# PCB_Project_Board_4.net
KiCad netlist of a schematic drawn in Altium Designer
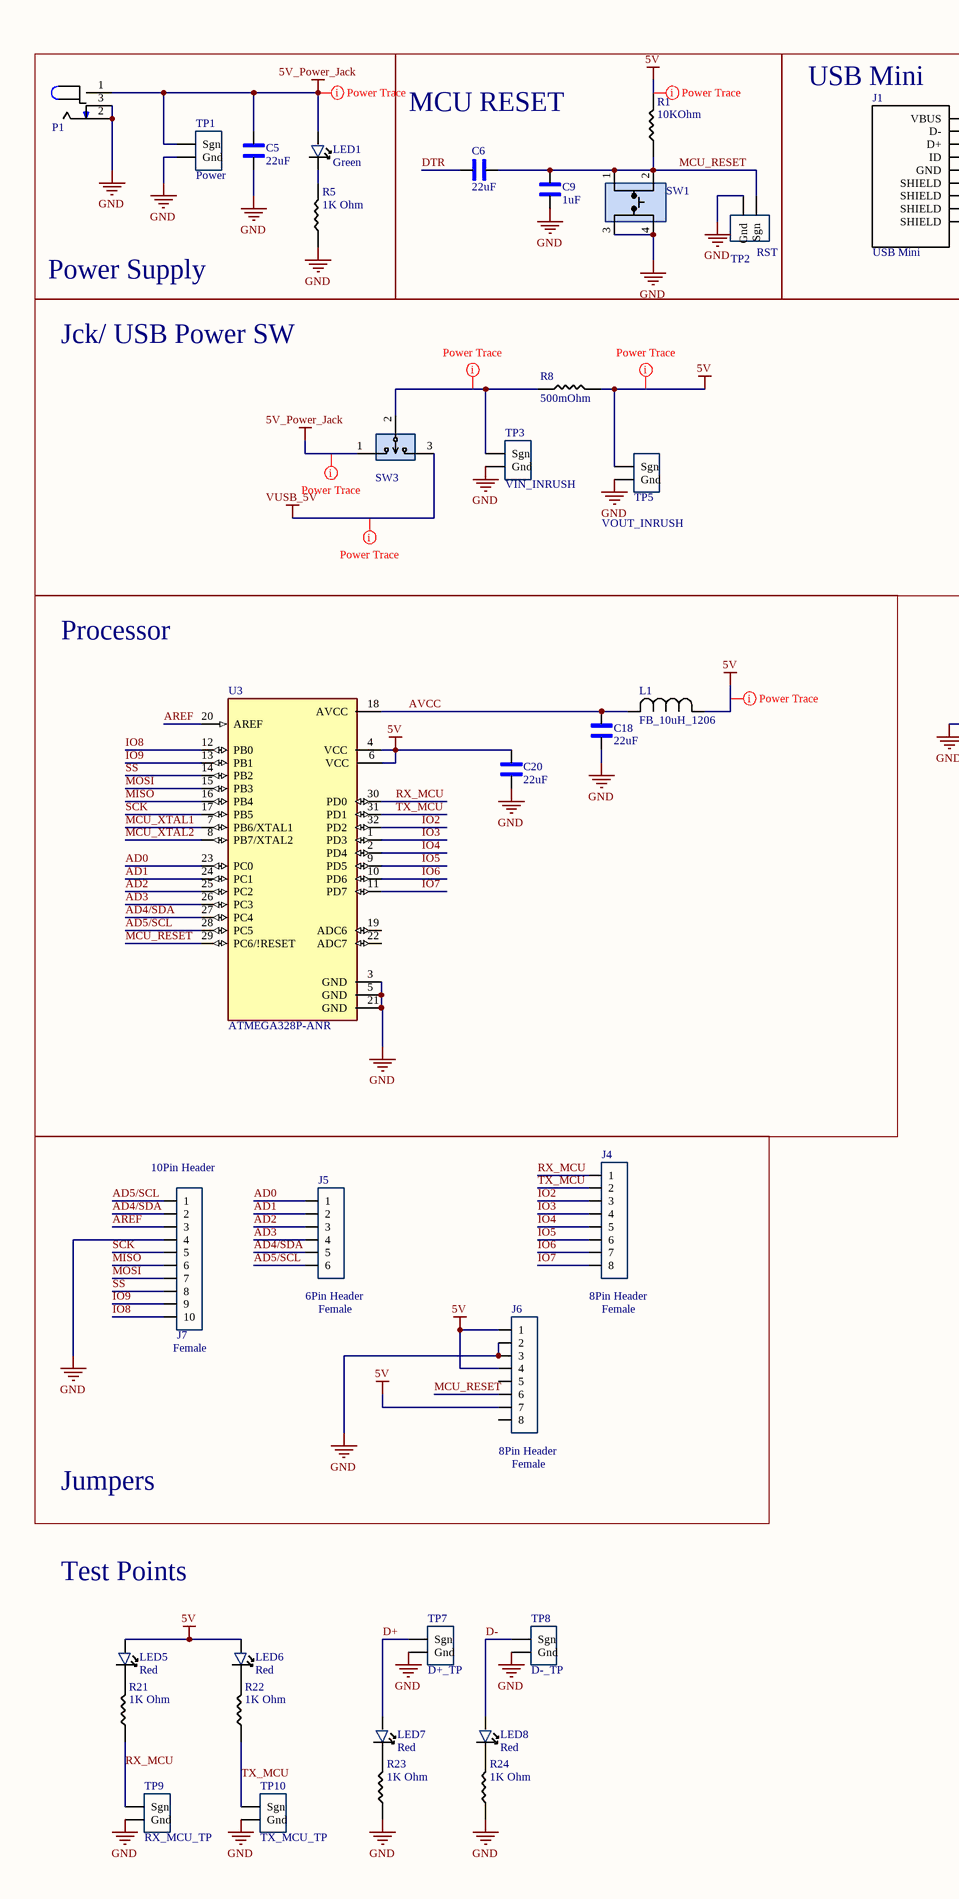
[diagram p0: PCB_Project_Board_4.SchDoc, left]
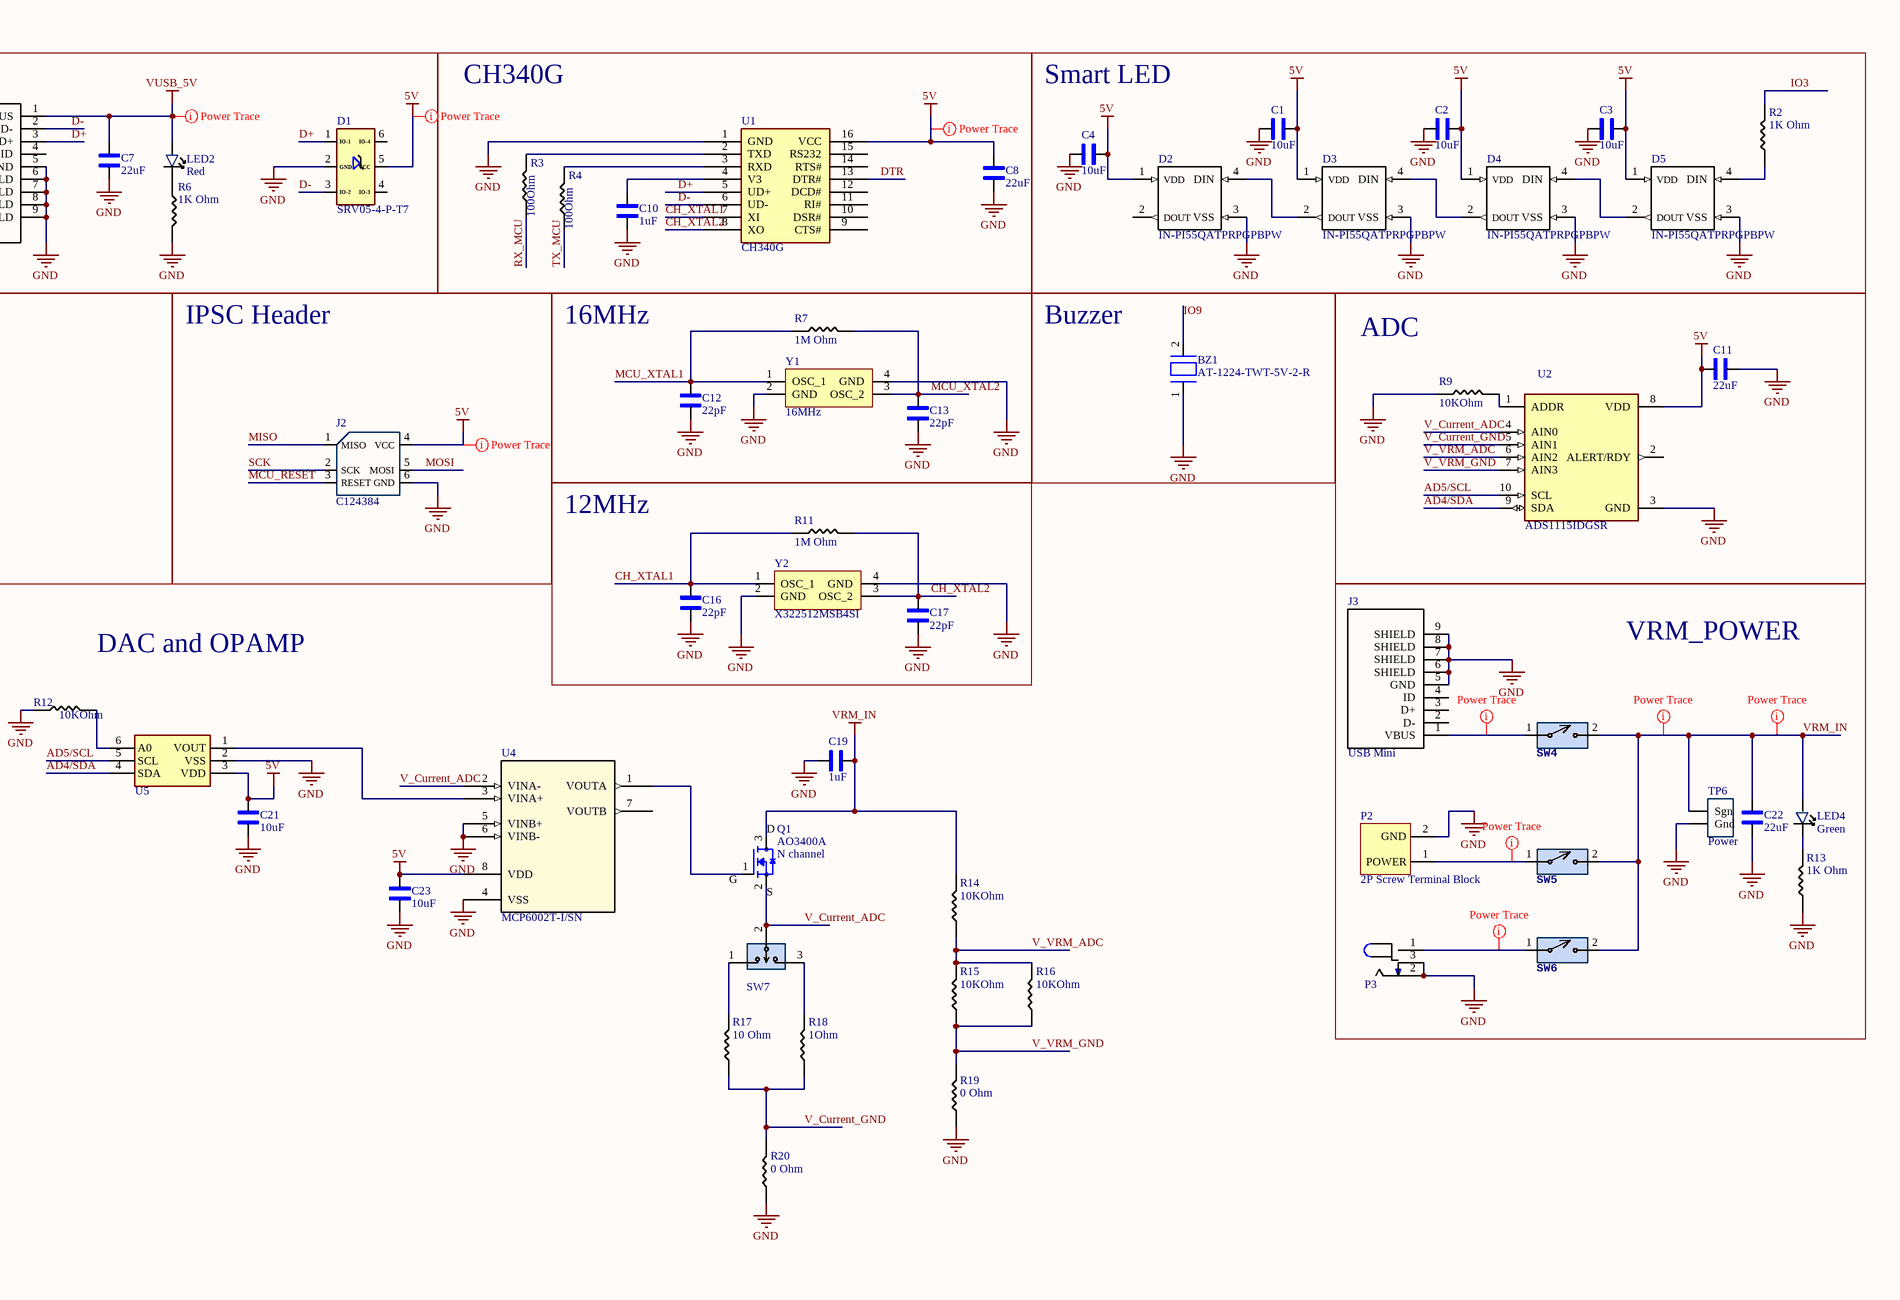
[diagram p1: PCB_Project_Board_4.SchDoc, right]

(export (version "E")
  (design (tool "Eeschema 10.0.6"))
  (components
    (comp (ref "BZ1")
      (value "AT-1224-TWT-5V-2-R")
      (footprint "BUZZER- TH")
      (fields (field (name "MFR PART #") "AT-1224-TWT-5V-2-R"))
      (libsource (lib "ECEN5730Lib_2023_01_DS") (part "BUZZER_1"))
    )
    (comp (ref "C1")
      (value "10uF")
      (footprint "1206_Passive_Capacitor")
      (description "10uF ±10% 50V X5R 1206 Multilayer Ceramic Capacitors MLCC - SMD/SMT RoHS")
      (fields (field (name "LCSC PART#") "C13585") (field (name "MFR PART #") "CL31A106KBHNNNE"))
      (libsource (lib "ECEN5730Lib_2023_01_DS") (part "C_10uF_1206"))
    )
    (comp (ref "C2")
      (value "10uF")
      (footprint "1206_Passive_Capacitor")
      (description "10uF ±10% 50V X5R 1206 Multilayer Ceramic Capacitors MLCC - SMD/SMT RoHS")
      (fields (field (name "LCSC PART#") "C13585") (field (name "MFR PART #") "CL31A106KBHNNNE"))
      (libsource (lib "ECEN5730Lib_2023_01_DS") (part "C_10uF_1206"))
    )
    (comp (ref "C3")
      (value "10uF")
      (footprint "1206_Passive_Capacitor")
      (description "10uF ±10% 50V X5R 1206 Multilayer Ceramic Capacitors MLCC - SMD/SMT RoHS")
      (fields (field (name "LCSC PART#") "C13585") (field (name "MFR PART #") "CL31A106KBHNNNE"))
      (libsource (lib "ECEN5730Lib_2023_01_DS") (part "C_10uF_1206"))
    )
    (comp (ref "C4")
      (value "10uF")
      (footprint "1206_Passive_Capacitor")
      (description "10uF ±10% 50V X5R 1206 Multilayer Ceramic Capacitors MLCC - SMD/SMT RoHS")
      (fields (field (name "LCSC PART#") "C13585") (field (name "MFR PART #") "CL31A106KBHNNNE"))
      (libsource (lib "ECEN5730Lib_2023_01_DS") (part "C_10uF_1206"))
    )
    (comp (ref "C5")
      (value "22uF")
      (footprint "1206_Passive_Capacitor")
      (description "22uF ±10% 25V X5R 1206 Multilayer Ceramic Capacitors MLCC - SMD/SMT RoHS")
      (fields (field (name "MFR PART #") "CL31A226KAHNNNE") (field (name "LCSC PART#") "C12891"))
      (libsource (lib "ECEN5730Lib_2023_01_DS") (part "C_22uF_1206"))
    )
    (comp (ref "C6")
      (value "22uF")
      (footprint "1206_Passive_Capacitor")
      (description "22uF ±10% 25V X5R 1206 Multilayer Ceramic Capacitors MLCC - SMD/SMT RoHS")
      (fields (field (name "MFR PART #") "CL31A226KAHNNNE") (field (name "LCSC PART#") "C12891"))
      (libsource (lib "ECEN5730Lib_2023_01_DS") (part "C_22uF_1206"))
    )
    (comp (ref "C7")
      (value "22uF")
      (footprint "1206_Passive_Capacitor")
      (description "22uF ±10% 25V X5R 1206 Multilayer Ceramic Capacitors MLCC - SMD/SMT RoHS")
      (fields (field (name "MFR PART #") "CL31A226KAHNNNE") (field (name "LCSC PART#") "C12891"))
      (libsource (lib "ECEN5730Lib_2023_01_DS") (part "C_22uF_1206"))
    )
    (comp (ref "C8")
      (value "22uF")
      (footprint "1206_Passive_Capacitor")
      (description "22uF ±10% 25V X5R 1206 Multilayer Ceramic Capacitors MLCC - SMD/SMT RoHS")
      (fields (field (name "MFR PART #") "CL31A226KAHNNNE") (field (name "LCSC PART#") "C12891"))
      (libsource (lib "ECEN5730Lib_2023_01_DS") (part "C_22uF_1206"))
    )
    (comp (ref "C9")
      (value "1uF")
      (footprint "1206_Passive_Capacitor")
      (description "MULTILAYER CERAMIC CAPACITORS MLCC - SMD/SMT 1UF 50V 1206 ROHS")
      (fields (field (name "MFR PART #") "CL31B105KBHNNNE") (field (name "LCSC PART#") "C1848"))
      (libsource (lib "ECEN5730Lib_2023_01_DS") (part "C_1uF_1206"))
    )
    (comp (ref "C10")
      (value "1uF")
      (footprint "1206_Passive_Capacitor")
      (description "MULTILAYER CERAMIC CAPACITORS MLCC - SMD/SMT 1UF 50V 1206 ROHS")
      (fields (field (name "MFR PART #") "CL31B105KBHNNNE") (field (name "LCSC PART#") "C1848"))
      (libsource (lib "ECEN5730Lib_2023_01_DS") (part "C_1uF_1206"))
    )
    (comp (ref "C11")
      (value "22uF")
      (footprint "1206_Passive_Capacitor")
      (description "22uF ±10% 25V X5R 1206 Multilayer Ceramic Capacitors MLCC - SMD/SMT RoHS")
      (fields (field (name "MFR PART #") "CL31A226KAHNNNE") (field (name "LCSC PART#") "C12891"))
      (libsource (lib "ECEN5730Lib_2023_01_DS") (part "C_22uF_1206"))
    )
    (comp (ref "C12")
      (value "22pF")
      (footprint "1206_Passive_Capacitor")
      (description "22pF ±5% 1kV C0G 1206 Multilayer Ceramic Capacitors MLCC - SMD/SMT RoHS")
      (fields (field (name "LCSC PART#") "C313096") (field (name "MFR PART #") "1206CG220J102NT"))
      (libsource (lib "ECEN5730Lib_2023_01_DS") (part "C_22pF_1206"))
    )
    (comp (ref "C13")
      (value "22pF")
      (footprint "1206_Passive_Capacitor")
      (description "22pF ±5% 1kV C0G 1206 Multilayer Ceramic Capacitors MLCC - SMD/SMT RoHS")
      (fields (field (name "LCSC PART#") "C313096") (field (name "MFR PART #") "1206CG220J102NT"))
      (libsource (lib "ECEN5730Lib_2023_01_DS") (part "C_22pF_1206"))
    )
    (comp (ref "C16")
      (value "22pF")
      (footprint "1206_Passive_Capacitor")
      (description "22pF ±5% 1kV C0G 1206 Multilayer Ceramic Capacitors MLCC - SMD/SMT RoHS")
      (fields (field (name "LCSC PART#") "C313096") (field (name "MFR PART #") "1206CG220J102NT"))
      (libsource (lib "ECEN5730Lib_2023_01_DS") (part "C_22pF_1206"))
    )
    (comp (ref "C17")
      (value "22pF")
      (footprint "1206_Passive_Capacitor")
      (description "22pF ±5% 1kV C0G 1206 Multilayer Ceramic Capacitors MLCC - SMD/SMT RoHS")
      (fields (field (name "LCSC PART#") "C313096") (field (name "MFR PART #") "1206CG220J102NT"))
      (libsource (lib "ECEN5730Lib_2023_01_DS") (part "C_22pF_1206"))
    )
    (comp (ref "C18")
      (value "22uF")
      (footprint "1206_Passive_Capacitor")
      (description "22uF ±10% 25V X5R 1206 Multilayer Ceramic Capacitors MLCC - SMD/SMT RoHS")
      (fields (field (name "MFR PART #") "CL31A226KAHNNNE") (field (name "LCSC PART#") "C12891"))
      (libsource (lib "ECEN5730Lib_2023_01_DS") (part "C_22uF_1206"))
    )
    (comp (ref "C19")
      (value "1uF")
      (footprint "1206_Passive_Capacitor")
      (description "MULTILAYER CERAMIC CAPACITORS MLCC - SMD/SMT 1UF 50V 1206 ROHS")
      (fields (field (name "MFR PART #") "CL31B105KBHNNNE") (field (name "LCSC PART#") "C1848"))
      (libsource (lib "ECEN5730Lib_2023_01_DS") (part "C_1uF_1206"))
    )
    (comp (ref "C20")
      (value "22uF")
      (footprint "1206_Passive_Capacitor")
      (description "22uF ±10% 25V X5R 1206 Multilayer Ceramic Capacitors MLCC - SMD/SMT RoHS")
      (fields (field (name "MFR PART #") "CL31A226KAHNNNE") (field (name "LCSC PART#") "C12891"))
      (libsource (lib "ECEN5730Lib_2023_01_DS") (part "C_22uF_1206"))
    )
    (comp (ref "C21")
      (value "10uF")
      (footprint "1206_Passive_Capacitor")
      (description "10uF ±10% 50V X5R 1206 Multilayer Ceramic Capacitors MLCC - SMD/SMT RoHS")
      (fields (field (name "LCSC PART#") "C13585") (field (name "MFR PART #") "CL31A106KBHNNNE"))
      (libsource (lib "ECEN5730Lib_2023_01_DS") (part "C_10uF_1206"))
    )
    (comp (ref "C22")
      (value "22uF")
      (footprint "1206_Passive_Capacitor")
      (description "22uF ±10% 25V X5R 1206 Multilayer Ceramic Capacitors MLCC - SMD/SMT RoHS")
      (fields (field (name "MFR PART #") "CL31A226KAHNNNE") (field (name "LCSC PART#") "C12891"))
      (libsource (lib "ECEN5730Lib_2023_01_DS") (part "C_22uF_1206"))
    )
    (comp (ref "C23")
      (value "10uF")
      (footprint "1206_Passive_Capacitor")
      (description "10uF ±10% 50V X5R 1206 Multilayer Ceramic Capacitors MLCC - SMD/SMT RoHS")
      (fields (field (name "LCSC PART#") "C13585") (field (name "MFR PART #") "CL31A106KBHNNNE"))
      (libsource (lib "ECEN5730Lib_2023_01_DS") (part "C_10uF_1206"))
    )
    (comp (ref "D1")
      (value "SRV05-4-P-T7")
      (footprint "TVS")
      (description "TVS SOT-23-6 ROHS")
      (fields (field (name "LCSC PART#") "C85364"))
      (libsource (lib "ECEN5730Lib_2023_01_DS") (part "D_TVS_Diode"))
    )
    (comp (ref "D2")
      (value "IN-PI55QATPRPGPBPW")
      (footprint "SERIAL_LED - duplicate")
      (fields
        (field (name "LCSC PART#") "C2761795")
        (field (name "MFR PART #") "IN-PI55QATPRPGPBPW-60")
        (field (name "MANUFACTURER") "Inolux")
      )
      (libsource (lib "ECEN5730Lib_2023_01_DS") (part "LED_Smart"))
    )
    (comp (ref "D3")
      (value "IN-PI55QATPRPGPBPW")
      (footprint "SERIAL_LED - duplicate")
      (fields
        (field (name "LCSC PART#") "C2761795")
        (field (name "MFR PART #") "IN-PI55QATPRPGPBPW-60")
        (field (name "MANUFACTURER") "Inolux")
      )
      (libsource (lib "ECEN5730Lib_2023_01_DS") (part "LED_Smart"))
    )
    (comp (ref "D4")
      (value "IN-PI55QATPRPGPBPW")
      (footprint "SERIAL_LED - duplicate")
      (fields
        (field (name "LCSC PART#") "C2761795")
        (field (name "MFR PART #") "IN-PI55QATPRPGPBPW-60")
        (field (name "MANUFACTURER") "Inolux")
      )
      (libsource (lib "ECEN5730Lib_2023_01_DS") (part "LED_Smart"))
    )
    (comp (ref "D5")
      (value "IN-PI55QATPRPGPBPW")
      (footprint "SERIAL_LED - duplicate")
      (fields
        (field (name "LCSC PART#") "C2761795")
        (field (name "MFR PART #") "IN-PI55QATPRPGPBPW-60")
        (field (name "MANUFACTURER") "Inolux")
      )
      (libsource (lib "ECEN5730Lib_2023_01_DS") (part "LED_Smart"))
    )
    (comp (ref "J1")
      (value "USB Mini")
      (footprint "USB_MINI_B")
      (description "Through Hole USB Connectors RoHS")
      (fields (field (name "LCSC PART#") "C46398") (field (name "MFR PART #") "920-462A2021D10102"))
      (libsource (lib "ECEN5730Lib_2023_01_DS") (part "J_USB_B_Mini"))
    )
    (comp (ref "J2")
      (value "NRPN032PAEN-RC")
      (footprint "ICSP")
      (description "Connector Header Through Hole 6 position 0.079\" (2.00mm)")
      (fields (field (name "LCSC PART#") "C124384"))
      (libsource (lib "ECEN5730Lib_2023_01_DS") (part "J_ICSP"))
    )
    (comp (ref "J3")
      (value "USB Mini")
      (footprint "USB_MINI_B")
      (description "Through Hole USB Connectors RoHS")
      (fields (field (name "LCSC PART#") "C46398") (field (name "MFR PART #") "920-462A2021D10102"))
      (libsource (lib "") (part "J_USB_B_Mini_1"))
    )
    (comp (ref "J4")
      (value "8Pin Header")
      (footprint "8_PIN_100MIL - Female")
      (description "8 Position Header Connector 0.100\" (2.54mm) Through Hole Tin")
      (fields
        (field (name "MFR PART #") "PPTC081LFBN-RC")
        (field (name "LCSC PART#") "C27438")
        (field (name "ALTIUM_VALUE") "Female")
      )
      (libsource (lib "ECEN5730Lib_2023_01_DS") (part "JF_8_PIN_FEMALE"))
    )
    (comp (ref "J5")
      (value "6Pin Header")
      (footprint "6_PIN_100MIL -Female")
      (description "6 Position Header Connector 0.100\" (2.54mm) Through Hole Tin")
      (fields
        (field (name "MFR PART #") "PPTC061LFBN-RC")
        (field (name "LCSC PART#") "C40877")
        (field (name "ALTIUM_VALUE") "Female")
      )
      (libsource (lib "ECEN5730Lib_2023_01_DS") (part "JF_6_PIN_FEMALE"))
    )
    (comp (ref "J6")
      (value "8Pin Header")
      (footprint "8_PIN_100MIL - Female")
      (description "8 Position Header Connector 0.100\" (2.54mm) Through Hole Tin")
      (fields
        (field (name "MFR PART #") "PPTC081LFBN-RC")
        (field (name "LCSC PART#") "C27438")
        (field (name "ALTIUM_VALUE") "Female")
      )
      (libsource (lib "ECEN5730Lib_2023_01_DS") (part "JF_8_PIN_FEMALE"))
    )
    (comp (ref "J7")
      (value "10Pin Header")
      (footprint "10_PIN_100MIL - Female")
      (description "10 Position Header Connector 0.100\" (2.54mm) Through Hole Tin")
      (fields
        (field (name "MFR PART #") "PPTC101LFBN-RC")
        (field (name "LCSC PART#") "C225507")
        (field (name "ALTIUM_VALUE") "Female")
      )
      (libsource (lib "ECEN5730Lib_2023_01_DS") (part "JF_10_PIN_FEMALE_"))
    )
    (comp (ref "L1")
      (value "FB_10uH_1206")
      (footprint "AIML-1206_ABR-M")
      (description "25mA 10uH ±10% 800mΩ 1206  Inductors (SMD) ROHS")
      (fields (field (name "MFR PART #") "CMI321609X100KT") (field (name "LCSC PART#") "C1051"))
      (libsource (lib "ECEN5730Lib_2023_01_DS") (part "FB_10uH_1206"))
    )
    (comp (ref "LED1")
      (value "Green")
      (footprint "LED_1206")
      (description "Green 513~528nm 1206 Light Emitting Diodes (LED) RoHS")
      (fields (field (name "MFR PART #") "SZYY1206G") (field (name "LCSC PART#") "C434439"))
      (libsource (lib "ECEN5730Lib_2023_01_DS") (part "LED_GREEN_1206"))
    )
    (comp (ref "LED2")
      (value "Red")
      (footprint "LED_1206")
      (description "Red 621~631nm 1206 Light Emitting Diodes (LED) RoHS")
      (fields (field (name "MFR PART #") "15-21/R6C-FQ1R1B/2T") (field (name "LCSC PART#") "C93133"))
      (libsource (lib "ECEN5730Lib_2023_01_DS") (part "LED_RED_1206"))
    )
    (comp (ref "LED4")
      (value "Green")
      (footprint "LED_1206")
      (description "Green 513~528nm 1206 Light Emitting Diodes (LED) RoHS")
      (fields (field (name "MFR PART #") "SZYY1206G") (field (name "LCSC PART#") "C434439"))
      (libsource (lib "ECEN5730Lib_2023_01_DS") (part "LED_GREEN_1206"))
    )
    (comp (ref "LED5")
      (value "Red")
      (footprint "LED_1206")
      (description "Red 621~631nm 1206 Light Emitting Diodes (LED) RoHS")
      (fields (field (name "MFR PART #") "15-21/R6C-FQ1R1B/2T") (field (name "LCSC PART#") "C93133"))
      (libsource (lib "ECEN5730Lib_2023_01_DS") (part "LED_RED_1206"))
    )
    (comp (ref "LED6")
      (value "Red")
      (footprint "LED_1206")
      (description "Red 621~631nm 1206 Light Emitting Diodes (LED) RoHS")
      (fields (field (name "MFR PART #") "15-21/R6C-FQ1R1B/2T") (field (name "LCSC PART#") "C93133"))
      (libsource (lib "ECEN5730Lib_2023_01_DS") (part "LED_RED_1206"))
    )
    (comp (ref "LED7")
      (value "Red")
      (footprint "LED_1206")
      (description "Red 621~631nm 1206 Light Emitting Diodes (LED) RoHS")
      (fields (field (name "MFR PART #") "15-21/R6C-FQ1R1B/2T") (field (name "LCSC PART#") "C93133"))
      (libsource (lib "ECEN5730Lib_2023_01_DS") (part "LED_RED_1206"))
    )
    (comp (ref "LED8")
      (value "Red")
      (footprint "LED_1206")
      (description "Red 621~631nm 1206 Light Emitting Diodes (LED) RoHS")
      (fields (field (name "MFR PART #") "15-21/R6C-FQ1R1B/2T") (field (name "LCSC PART#") "C93133"))
      (libsource (lib "ECEN5730Lib_2023_01_DS") (part "LED_RED_1206"))
    )
    (comp (ref "P1")
      (value "Power Jack")
      (footprint "Power_Jack")
      (description "Power Barrel Connector Jack 2.10mm ID (0.083\"), 5.50mm OD (0.217\") Through Hole, Right Angle")
      (fields (field (name "MFR PART #") "PJ-102A") (field (name "LCSC PART#") "C136744"))
      (libsource (lib "ECEN5730Lib_2023_01_DS") (part "P_Power Jack"))
    )
    (comp (ref "P2")
      (value "2P Screw Terminal Block")
      (footprint "P_Terminal block 3.5mm-pitch")
      (description "Green Straight pin 3.5mm  pitch; P=3.5mm  Screw terminal ROHS")
      (fields (field (name "MFR PART #") "KF350-3.5-2P") (field (name "MANUFACTURER") "Cixi Kefa Elec"))
      (libsource (lib "ECEN5730Lib_2023_01_DS") (part "P_Terminal block"))
    )
    (comp (ref "P3")
      (value "Power Jack")
      (footprint "Power_Jack")
      (description "Power Barrel Connector Jack 2.10mm ID (0.083\"), 5.50mm OD (0.217\") Through Hole, Right Angle")
      (fields (field (name "MFR PART #") "PJ-102A") (field (name "LCSC PART#") "C136744"))
      (libsource (lib "ECEN5730Lib_2023_01_DS") (part "P_Power Jack"))
    )
    (comp (ref "Q1")
      (value "AO3400A")
      (footprint "N-MOSFET")
      (description "MOSFET N Trench 30V 5.7A 1.5V @ 250uA 26.5 m? @ 5.7A,10V SOT-23-3L RoHS")
      (fields (field (name "LCSC PART#") "C20917") (field (name "ALTIUM_VALUE") "N channel"))
      (libsource (lib "ECEN5730Lib_2023_01_DS") (part "Q_Nch_MOSFET"))
    )
    (comp (ref "R1")
      (value "10KOhm")
      (footprint "1206_Passive_Resitor")
      (description "10 kOhms ±5% 0.25W, 1/4W Chip Resistor 1206 (3216 Metric) Automotive AEC-Q200 Thick Film")
      (fields (field (name "MFR PART #") "RMCF1206FT10K0") (field (name "LCSC PART#") "C17902"))
      (libsource (lib "ECEN5730Lib_2023_01_DS") (part "R_10KOhm_1206"))
    )
    (comp (ref "R2")
      (value "1K Ohm")
      (footprint "1206_Passive_Resitor")
      (description "CHIP RESISTOR - SURFACE MOUNT 1KOHMS ±1% 1/4W 1206 ROHS")
      (fields (field (name "MFR PART #") "RNCP1206FTD1K00CT") (field (name "LCSC PART#") "C4410"))
      (libsource (lib "ECEN5730Lib_2023_01_DS") (part "R_1K_1206"))
    )
    (comp (ref "R3")
      (value "100Ohm")
      (footprint "1206_Passive_Resitor")
      (description "100Ω ±1% 0.25W ±100ppm/℃ 1206 Chip Resistor - Surface Mount RoHS")
      (fields (field (name "LCSC PART#") "C17901") (field (name "MFR PART #") "1206W4F1000T5E"))
      (libsource (lib "ECEN5730Lib_2023_01_DS") (part "R_100Ohm_1206"))
    )
    (comp (ref "R4")
      (value "100Ohm")
      (footprint "1206_Passive_Resitor")
      (description "100Ω ±1% 0.25W ±100ppm/℃ 1206 Chip Resistor - Surface Mount RoHS")
      (fields (field (name "LCSC PART#") "C17901") (field (name "MFR PART #") "1206W4F1000T5E"))
      (libsource (lib "ECEN5730Lib_2023_01_DS") (part "R_100Ohm_1206"))
    )
    (comp (ref "R5")
      (value "1K Ohm")
      (footprint "1206_Passive_Resitor")
      (description "CHIP RESISTOR - SURFACE MOUNT 1KOHMS ±1% 1/4W 1206 ROHS")
      (fields (field (name "MFR PART #") "RNCP1206FTD1K00CT") (field (name "LCSC PART#") "C4410"))
      (libsource (lib "ECEN5730Lib_2023_01_DS") (part "R_1K_1206"))
    )
    (comp (ref "R6")
      (value "1K Ohm")
      (footprint "1206_Passive_Resitor")
      (description "CHIP RESISTOR - SURFACE MOUNT 1KOHMS ±1% 1/4W 1206 ROHS")
      (fields (field (name "MFR PART #") "RNCP1206FTD1K00CT") (field (name "LCSC PART#") "C4410"))
      (libsource (lib "ECEN5730Lib_2023_01_DS") (part "R_1K_1206"))
    )
    (comp (ref "R7")
      (value "1M Ohm")
      (footprint "1206_Passive_Resitor")
      (description "CHIP RESISTOR - SURFACE MOUNT 1MOHMS ±1% 1/4W 1206 ROHS")
      (fields (field (name "MFR PART #") "RMCF1206JT1M00") (field (name "LCSC PART#") "C17927"))
      (libsource (lib "ECEN5730Lib_2023_01_DS") (part "R_1M_1206"))
    )
    (comp (ref "R8")
      (value "500mOhm")
      (footprint "1206_Passive_Resitor")
      (description "Resistors/Shunt 250mW 500mΩ ±800ppm/℃ ±5% 1206  Current Sense  Resistors ROHS")
      (fields (field (name "MFR PART #") "1206W4J050KT5E") (field (name "LCSC PART#") "C247433"))
      (libsource (lib "ECEN5730Lib_2023_01_DS") (part "R_500mOhm_1206"))
    )
    (comp (ref "R9")
      (value "10KOhm")
      (footprint "1206_Passive_Resitor")
      (description "10 kOhms ±5% 0.25W, 1/4W Chip Resistor 1206 (3216 Metric) Automotive AEC-Q200 Thick Film")
      (fields (field (name "MFR PART #") "RMCF1206FT10K0") (field (name "LCSC PART#") "C17902"))
      (libsource (lib "ECEN5730Lib_2023_01_DS") (part "R_10KOhm_1206"))
    )
    (comp (ref "R11")
      (value "1M Ohm")
      (footprint "1206_Passive_Resitor")
      (description "CHIP RESISTOR - SURFACE MOUNT 1MOHMS ±1% 1/4W 1206 ROHS")
      (fields (field (name "MFR PART #") "RMCF1206JT1M00") (field (name "LCSC PART#") "C17927"))
      (libsource (lib "ECEN5730Lib_2023_01_DS") (part "R_1M_1206"))
    )
    (comp (ref "R12")
      (value "10KOhm")
      (footprint "1206_Passive_Resitor")
      (description "10 kOhms ±5% 0.25W, 1/4W Chip Resistor 1206 (3216 Metric) Automotive AEC-Q200 Thick Film")
      (fields (field (name "MFR PART #") "RMCF1206FT10K0") (field (name "LCSC PART#") "C17902"))
      (libsource (lib "ECEN5730Lib_2023_01_DS") (part "R_10KOhm_1206"))
    )
    (comp (ref "R13")
      (value "1K Ohm")
      (footprint "1206_Passive_Resitor")
      (description "CHIP RESISTOR - SURFACE MOUNT 1KOHMS ±1% 1/4W 1206 ROHS")
      (fields (field (name "MFR PART #") "RNCP1206FTD1K00CT") (field (name "LCSC PART#") "C4410"))
      (libsource (lib "ECEN5730Lib_2023_01_DS") (part "R_1K_1206"))
    )
    (comp (ref "R14")
      (value "10KOhm")
      (footprint "1206_Passive_Resitor")
      (description "10 kOhms ±5% 0.25W, 1/4W Chip Resistor 1206 (3216 Metric) Automotive AEC-Q200 Thick Film")
      (fields (field (name "MFR PART #") "RMCF1206FT10K0") (field (name "LCSC PART#") "C17902"))
      (libsource (lib "ECEN5730Lib_2023_01_DS") (part "R_10KOhm_1206"))
    )
    (comp (ref "R15")
      (value "10KOhm")
      (footprint "1206_Passive_Resitor")
      (description "10 kOhms ±5% 0.25W, 1/4W Chip Resistor 1206 (3216 Metric) Automotive AEC-Q200 Thick Film")
      (fields (field (name "MFR PART #") "RMCF1206FT10K0") (field (name "LCSC PART#") "C17902"))
      (libsource (lib "ECEN5730Lib_2023_01_DS") (part "R_10KOhm_1206"))
    )
    (comp (ref "R16")
      (value "10KOhm")
      (footprint "1206_Passive_Resitor")
      (description "10 kOhms ±5% 0.25W, 1/4W Chip Resistor 1206 (3216 Metric) Automotive AEC-Q200 Thick Film")
      (fields (field (name "MFR PART #") "RMCF1206FT10K0") (field (name "LCSC PART#") "C17902"))
      (libsource (lib "ECEN5730Lib_2023_01_DS") (part "R_10KOhm_1206"))
    )
    (comp (ref "R17")
      (value "10 Ohm")
      (footprint "1206_Passive_Resitor")
      (description "CHIP RESISTOR - SURFACE MOUNT 0.1OHMS ±1% 1/4W 1206 ROHS")
      (fields (field (name "MFR PART #") "1206W4F100JT5E") (field (name "LCSC PART#") "C17903"))
      (libsource (lib "ECEN5730Lib_2023_01_DS") (part "R_10Ohm_1206"))
    )
    (comp (ref "R18")
      (value "1Ohm")
      (footprint "1206_Passive_Resitor")
      (description "1Ω ±5% 0.25W ±400ppm/℃ 1206 Chip Resistor - Surface Mount RoHS")
      (fields (field (name "LCSC PART#") "C1409") (field (name "MFR PART #") "1206W4J010JT5E"))
      (libsource (lib "ECEN5730Lib_2023_01_DS") (part "R_1Ohm_1206"))
    )
    (comp (ref "R19")
      (value "0 Ohm")
      (footprint "1206_Passive_Resitor")
      (description "CHIP RESISTOR - SURFACE MOUNT 0OHMS ±1% 1/4W 1206 ROHS")
      (fields (field (name "MFR PART #") "1206W4F0000T5E") (field (name "LCSC PART#") "C17888"))
      (libsource (lib "ECEN5730Lib_2023_01_DS") (part "R_0Ohm_1206"))
    )
    (comp (ref "R20")
      (value "0 Ohm")
      (footprint "1206_Passive_Resitor")
      (description "CHIP RESISTOR - SURFACE MOUNT 0OHMS ±1% 1/4W 1206 ROHS")
      (fields (field (name "MFR PART #") "1206W4F0000T5E") (field (name "LCSC PART#") "C17888"))
      (libsource (lib "ECEN5730Lib_2023_01_DS") (part "R_0Ohm_1206"))
    )
    (comp (ref "R21")
      (value "1K Ohm")
      (footprint "1206_Passive_Resitor")
      (description "CHIP RESISTOR - SURFACE MOUNT 1KOHMS ±1% 1/4W 1206 ROHS")
      (fields (field (name "MFR PART #") "RNCP1206FTD1K00CT") (field (name "LCSC PART#") "C4410"))
      (libsource (lib "ECEN5730Lib_2023_01_DS") (part "R_1K_1206"))
    )
    (comp (ref "R22")
      (value "1K Ohm")
      (footprint "1206_Passive_Resitor")
      (description "CHIP RESISTOR - SURFACE MOUNT 1KOHMS ±1% 1/4W 1206 ROHS")
      (fields (field (name "MFR PART #") "RNCP1206FTD1K00CT") (field (name "LCSC PART#") "C4410"))
      (libsource (lib "ECEN5730Lib_2023_01_DS") (part "R_1K_1206"))
    )
    (comp (ref "R23")
      (value "1K Ohm")
      (footprint "1206_Passive_Resitor")
      (description "CHIP RESISTOR - SURFACE MOUNT 1KOHMS ±1% 1/4W 1206 ROHS")
      (fields (field (name "MFR PART #") "RNCP1206FTD1K00CT") (field (name "LCSC PART#") "C4410"))
      (libsource (lib "ECEN5730Lib_2023_01_DS") (part "R_1K_1206"))
    )
    (comp (ref "R24")
      (value "1K Ohm")
      (footprint "1206_Passive_Resitor")
      (description "CHIP RESISTOR - SURFACE MOUNT 1KOHMS ±1% 1/4W 1206 ROHS")
      (fields (field (name "MFR PART #") "RNCP1206FTD1K00CT") (field (name "LCSC PART#") "C4410"))
      (libsource (lib "ECEN5730Lib_2023_01_DS") (part "R_1K_1206"))
    )
    (comp (ref "SW1")
      (value "TL3305AF160QG")
      (footprint "Switch_JLC")
      (description "Tactile Switch SPST-NO Top Actuated Surface Mount")
      (fields (field (name "MFR PART #") "KH-4.5X4.5X4.3H-STM") (field (name "LCSC PART#") "C2837550"))
      (libsource (lib "ECEN5730Lib_2023_01_DS") (part "SW_Push_Button_JLC"))
    )
    (comp (ref "SW3")
      (value "PREC003SAAN-RC")
      (footprint "3_PIN_100mil")
      (description "Connector Header Through Hole 3 position 0.100\" (2.54mm)")
      (fields (field (name "LCSC PART#") "C49257"))
      (libsource (lib "ECEN5730Lib_2023_01_DS") (part "SW_3Pin_100mil_Switch"))
    )
    (comp (ref "SW4")
      (value "SW_2Pin_100mil_Switch")
      (footprint "2Pin-Header-Conn")
      (description "2Pin Header")
      (fields (field (name "LCSC PART#") "C124375"))
      (libsource (lib "ECEN5730Lib_2023_01_DS") (part "SW_2Pin_100mil_Switch"))
    )
    (comp (ref "SW5")
      (value "SW_2Pin_100mil_Switch")
      (footprint "2Pin-Header-Conn")
      (description "2Pin Header")
      (fields (field (name "LCSC PART#") "C124375"))
      (libsource (lib "ECEN5730Lib_2023_01_DS") (part "SW_2Pin_100mil_Switch"))
    )
    (comp (ref "SW6")
      (value "SW_2Pin_100mil_Switch")
      (footprint "2Pin-Header-Conn")
      (description "2Pin Header")
      (fields (field (name "LCSC PART#") "C124375"))
      (libsource (lib "ECEN5730Lib_2023_01_DS") (part "SW_2Pin_100mil_Switch"))
    )
    (comp (ref "SW7")
      (value "PREC003SAAN-RC")
      (footprint "3_PIN_100mil")
      (description "Connector Header Through Hole 3 position 0.100\" (2.54mm)")
      (fields (field (name "LCSC PART#") "C49257"))
      (libsource (lib "ECEN5730Lib_2023_01_DS") (part "SW_3Pin_100mil_Switch"))
    )
    (comp (ref "TP1")
      (value "Power")
      (footprint "TP10x_Probe")
      (description "Test Point 300 mil centers")
      (libsource (lib "ECEN5730Lib_2023_01_DS") (part "TP_10x_Probe"))
    )
    (comp (ref "TP2")
      (value "RST")
      (footprint "TP10x_Probe")
      (description "Test Point 300 mil centers")
      (libsource (lib "") (part "TP_10x_Probe_1"))
    )
    (comp (ref "TP3")
      (value "VIN_INRUSH")
      (footprint "TP10x_Probe")
      (description "Test Point 300 mil centers")
      (libsource (lib "ECEN5730Lib_2023_01_DS") (part "TP_10x_Probe"))
    )
    (comp (ref "TP5")
      (value "VOUT_INRUSH")
      (footprint "TP10x_Probe")
      (description "Test Point 300 mil centers")
      (libsource (lib "ECEN5730Lib_2023_01_DS") (part "TP_10x_Probe"))
    )
    (comp (ref "TP6")
      (value "Power")
      (footprint "TP10x_Probe")
      (description "Test Point 300 mil centers")
      (libsource (lib "ECEN5730Lib_2023_01_DS") (part "TP_10x_Probe"))
    )
    (comp (ref "TP7")
      (value "D+_TP")
      (footprint "TP10x_Probe")
      (description "Test Point 300 mil centers")
      (libsource (lib "ECEN5730Lib_2023_01_DS") (part "TP_10x_Probe"))
    )
    (comp (ref "TP8")
      (value "D-_TP")
      (footprint "TP10x_Probe")
      (description "Test Point 300 mil centers")
      (libsource (lib "ECEN5730Lib_2023_01_DS") (part "TP_10x_Probe"))
    )
    (comp (ref "TP9")
      (value "RX_MCU_TP")
      (footprint "TP10x_Probe")
      (description "Test Point 300 mil centers")
      (libsource (lib "ECEN5730Lib_2023_01_DS") (part "TP_10x_Probe"))
    )
    (comp (ref "TP10")
      (value "TX_MCU_TP")
      (footprint "TP10x_Probe")
      (description "Test Point 300 mil centers")
      (libsource (lib "ECEN5730Lib_2023_01_DS") (part "TP_10x_Probe"))
    )
    (comp (ref "U1")
      (value "CH340G")
      (footprint "USB to serial")
      (description "Transceiver USB 2.0 2Mbps SOP-16_150mil USB ICs RoHS")
      (fields (field (name "LCSC PART#") "C14267"))
      (libsource (lib "ECEN5730Lib_2023_01_DS") (part "U_USBtoSerial"))
    )
    (comp (ref "U2")
      (value "ADS1115IDGSR")
      (footprint "ADC_ADS1115IDGSR")
      (description "16-Bit ADC with Integrated MUX, PGA, Comparator, Oscillator, and Reference 10-VSSOP -40 to 125")
      (fields (field (name "LCSC PART#") "C37593"))
      (libsource (lib "ECEN5730Lib_2023_01_DS") (part "U_ADC_ADS1115IDGSR"))
    )
    (comp (ref "U3")
      (value "ATMEGA328P-ANR")
      (footprint "ATMega328P")
      (description "AVR AVR® ATmega Microcontroller IC 8-Bit 20MHz 32KB (16K x 16) FLASH 32-TQFP (7x7)")
      (fields (field (name "MFR PART #") "ATMEGA328P-AU") (field (name "LCSC PART#") "C14877"))
      (libsource (lib "ECEN5730Lib_2023_01_DS") (part "U_ATMega328P"))
    )
    (comp (ref "U4")
      (value "MCP6002T-I/SN")
      (footprint "SOIC127P600X175-8N")
      (description "0.6 V/us 2 1MHz 1.8V ~ 6V 100μA General Purpose SOIC-8_150mil  Operational Amplifier ROHS")
      (fields (field (name "MFR") "Microchip") (field (name "LCSC PART#") "C7377"))
      (libsource (lib "ECEN5730Lib_2023_01_DS") (part "U_MCP6002T-I/SN"))
    )
    (comp (ref "U5")
      (value "DAC IC")
      (footprint "MCP4725")
      (description "IC DAC 12BIT V-OUT SOT23-6")
      (fields (field (name "LCSC PART#") "C144198") (field (name "MFR PART #") "MCP4725A0T-E/CH"))
      (libsource (lib "ECEN5730Lib_2023_01_DS") (part "U_MCP4725A0T-E/CH"))
    )
    (comp (ref "Y1")
      (value "16MHz")
      (footprint "Crystal resonator")
      (description "±10ppm 16000000Hz -40℃~85℃ 贴片无源晶振 60Ω 9pF SMD3225-4P Crystals ROHS")
      (fields (field (name "LCSC PART#") "C13738") (field (name "MFR PART #") "X322516MLB4SI"))
      (libsource (lib "ECEN5730Lib_2023_01_DS") (part "X_16Mhz_Res"))
    )
    (comp (ref "Y2")
      (value "X322512MSB4SI")
      (footprint "Crystal resonator")
      (description "SMD Crystal Resonators 12MHz ±10ppm SMD-3225_4P RoHS")
      (fields (field (name "LCSC PART#") "C9002"))
      (libsource (lib "ECEN5730Lib_2023_01_DS") (part "X_12MHz_Res"))
    )
  )
  (nets
    (net (code "1") (name "/AD0") (class "Default")
      (node (ref "J5") (pin "1") (pinfunction "1_1") (pintype "passive"))
      (node (ref "U3") (pin "23") (pinfunction "PC0_23") (pintype "bidirectional"))
    )
    (net (code "2") (name "/AD1") (class "Default")
      (node (ref "J5") (pin "2") (pinfunction "2_2") (pintype "passive"))
      (node (ref "U3") (pin "24") (pinfunction "PC1_24") (pintype "bidirectional"))
    )
    (net (code "3") (name "/AD2") (class "Default")
      (node (ref "J5") (pin "3") (pinfunction "3_3") (pintype "passive"))
      (node (ref "U3") (pin "25") (pinfunction "PC2_25") (pintype "bidirectional"))
    )
    (net (code "4") (name "/AD3") (class "Default")
      (node (ref "J5") (pin "4") (pinfunction "4_4") (pintype "passive"))
      (node (ref "U3") (pin "26") (pinfunction "PC3_26") (pintype "bidirectional"))
    )
    (net (code "5") (name "/AD4{slash}SDA") (class "Default")
      (node (ref "J5") (pin "5") (pinfunction "5_5") (pintype "passive"))
      (node (ref "J7") (pin "2") (pinfunction "2_2") (pintype "passive"))
      (node (ref "U2") (pin "9") (pinfunction "SDA_9") (pintype "bidirectional"))
      (node (ref "U3") (pin "27") (pinfunction "PC4_27") (pintype "bidirectional"))
      (node (ref "U5") (pin "4") (pinfunction "SDA_4") (pintype "passive"))
    )
    (net (code "6") (name "/AD5{slash}SCL") (class "Default")
      (node (ref "J5") (pin "6") (pinfunction "6_6") (pintype "passive"))
      (node (ref "J7") (pin "1") (pinfunction "1_1") (pintype "passive"))
      (node (ref "U2") (pin "10") (pinfunction "SCL_10") (pintype "input"))
      (node (ref "U3") (pin "28") (pinfunction "PC5_28") (pintype "bidirectional"))
      (node (ref "U5") (pin "5") (pinfunction "SCL_5") (pintype "passive"))
    )
    (net (code "7") (name "/AREF") (class "Default")
      (node (ref "J7") (pin "3") (pinfunction "3_3") (pintype "passive"))
      (node (ref "U3") (pin "20") (pinfunction "AREF_20") (pintype "input"))
    )
    (net (code "8") (name "/AVCC") (class "Default")
      (node (ref "C18") (pin "2") (pinfunction "2_2") (pintype "passive"))
      (node (ref "L1") (pin "2") (pinfunction "2_2") (pintype "passive"))
      (node (ref "U3") (pin "18") (pinfunction "AVCC_18") (pintype "power_in"))
    )
    (net (code "9") (name "/CH_XTAL1") (class "Default")
      (node (ref "C16") (pin "2") (pinfunction "2_2") (pintype "passive"))
      (node (ref "R11") (pin "1") (pinfunction "1_1") (pintype "passive"))
      (node (ref "U1") (pin "7") (pinfunction "XI_7") (pintype "passive"))
      (node (ref "Y2") (pin "1") (pinfunction "OSC_1_1") (pintype "passive"))
    )
    (net (code "10") (name "/CH_XTAL2") (class "Default")
      (node (ref "C17") (pin "2") (pinfunction "2_2") (pintype "passive"))
      (node (ref "R11") (pin "2") (pinfunction "2_2") (pintype "passive"))
      (node (ref "U1") (pin "8") (pinfunction "XO_8") (pintype "passive"))
      (node (ref "Y2") (pin "3") (pinfunction "OSC_2_3") (pintype "passive"))
    )
    (net (code "11") (name "/D+") (class "Default")
      (node (ref "D1") (pin "1") (pinfunction "IO-1_1") (pintype "passive"))
      (node (ref "J1") (pin "3") (pinfunction "D+_3") (pintype "passive"))
      (node (ref "LED7") (pin "1") (pinfunction "1_1") (pintype "passive"))
      (node (ref "TP7") (pin "1") (pinfunction "Sgn_1") (pintype "passive"))
      (node (ref "U1") (pin "5") (pinfunction "UD+_5") (pintype "passive"))
    )
    (net (code "12") (name "/D-") (class "Default")
      (node (ref "D1") (pin "3") (pinfunction "IO-2_3") (pintype "passive"))
      (node (ref "J1") (pin "2") (pinfunction "D-_2") (pintype "passive"))
      (node (ref "LED8") (pin "1") (pinfunction "1_1") (pintype "passive"))
      (node (ref "TP8") (pin "1") (pinfunction "Sgn_1") (pintype "passive"))
      (node (ref "U1") (pin "6") (pinfunction "UD-_6") (pintype "passive"))
    )
    (net (code "13") (name "/DTR") (class "Default")
      (node (ref "C6") (pin "1") (pinfunction "1_1") (pintype "passive"))
      (node (ref "U1") (pin "13") (pinfunction "DTR#_13") (pintype "passive"))
    )
    (net (code "14") (name "/IO2") (class "Default")
      (node (ref "J4") (pin "3") (pinfunction "3_3") (pintype "passive"))
      (node (ref "U3") (pin "32") (pinfunction "PD2_32") (pintype "bidirectional"))
    )
    (net (code "15") (name "/IO3") (class "Default")
      (node (ref "J4") (pin "4") (pinfunction "4_4") (pintype "passive"))
      (node (ref "R2") (pin "2") (pinfunction "2_2") (pintype "passive"))
      (node (ref "U3") (pin "1") (pinfunction "PD3_1") (pintype "bidirectional"))
    )
    (net (code "16") (name "/IO4") (class "Default")
      (node (ref "J4") (pin "5") (pinfunction "5_5") (pintype "passive"))
      (node (ref "U3") (pin "2") (pinfunction "PD4_2") (pintype "bidirectional"))
    )
    (net (code "17") (name "/IO5") (class "Default")
      (node (ref "J4") (pin "6") (pinfunction "6_6") (pintype "passive"))
      (node (ref "U3") (pin "9") (pinfunction "PD5_9") (pintype "bidirectional"))
    )
    (net (code "18") (name "/IO6") (class "Default")
      (node (ref "J4") (pin "7") (pinfunction "7_7") (pintype "passive"))
      (node (ref "U3") (pin "10") (pinfunction "PD6_10") (pintype "bidirectional"))
    )
    (net (code "19") (name "/IO7") (class "Default")
      (node (ref "J4") (pin "8") (pinfunction "8_8") (pintype "passive"))
      (node (ref "U3") (pin "11") (pinfunction "PD7_11") (pintype "bidirectional"))
    )
    (net (code "20") (name "/IO8") (class "Default")
      (node (ref "J7") (pin "10") (pinfunction "10_10") (pintype "passive"))
      (node (ref "U3") (pin "12") (pinfunction "PB0_12") (pintype "bidirectional"))
    )
    (net (code "21") (name "/IO9") (class "Default")
      (node (ref "BZ1") (pin "2") (pinfunction "BZ2_2") (pintype "passive"))
      (node (ref "J7") (pin "9") (pinfunction "9_9") (pintype "passive"))
      (node (ref "U3") (pin "13") (pinfunction "PB1_13") (pintype "bidirectional"))
    )
    (net (code "22") (name "/MCU_RESET") (class "Default")
      (node (ref "C6") (pin "2") (pinfunction "2_2") (pintype "passive"))
      (node (ref "C9") (pin "2") (pinfunction "2_2") (pintype "passive"))
      (node (ref "J2") (pin "3") (pinfunction "RESET_3") (pintype "passive"))
      (node (ref "J6") (pin "6") (pinfunction "6_6") (pintype "passive"))
      (node (ref "R1") (pin "1") (pinfunction "1_1") (pintype "passive"))
      (node (ref "SW1") (pin "1") (pinfunction "1_1") (pintype "passive"))
      (node (ref "SW1") (pin "2") (pinfunction "2_2") (pintype "passive"))
      (node (ref "TP2") (pin "1") (pinfunction "Sgn_1") (pintype "passive"))
      (node (ref "U3") (pin "29") (pinfunction "PC6/!RESET_29") (pintype "bidirectional"))
    )
    (net (code "23") (name "/MCU_XTAL1") (class "Default")
      (node (ref "C12") (pin "2") (pinfunction "2_2") (pintype "passive"))
      (node (ref "R7") (pin "1") (pinfunction "1_1") (pintype "passive"))
      (node (ref "U3") (pin "7") (pinfunction "PB6/XTAL1_7") (pintype "bidirectional"))
      (node (ref "Y1") (pin "1") (pinfunction "OSC_1_1") (pintype "passive"))
    )
    (net (code "24") (name "/MCU_XTAL2") (class "Default")
      (node (ref "C13") (pin "2") (pinfunction "2_2") (pintype "passive"))
      (node (ref "R7") (pin "2") (pinfunction "2_2") (pintype "passive"))
      (node (ref "U3") (pin "8") (pinfunction "PB7/XTAL2_8") (pintype "bidirectional"))
      (node (ref "Y1") (pin "3") (pinfunction "OSC_2_3") (pintype "passive"))
    )
    (net (code "25") (name "/MISO") (class "Default")
      (node (ref "J2") (pin "1") (pinfunction "MISO_1") (pintype "passive"))
      (node (ref "J7") (pin "6") (pinfunction "6_6") (pintype "passive"))
      (node (ref "U3") (pin "16") (pinfunction "PB4_16") (pintype "bidirectional"))
    )
    (net (code "26") (name "/MOSI") (class "Default")
      (node (ref "J2") (pin "5") (pinfunction "MOSI_5") (pintype "passive"))
      (node (ref "J7") (pin "7") (pinfunction "7_7") (pintype "passive"))
      (node (ref "U3") (pin "15") (pinfunction "PB3_15") (pintype "bidirectional"))
    )
    (net (code "27") (name "/RX_MCU") (class "Default")
      (node (ref "J4") (pin "1") (pinfunction "1_1") (pintype "passive"))
      (node (ref "R21") (pin "1") (pinfunction "1_1") (pintype "passive"))
      (node (ref "R3") (pin "1") (pinfunction "1_1") (pintype "passive"))
      (node (ref "TP9") (pin "1") (pinfunction "Sgn_1") (pintype "passive"))
      (node (ref "U3") (pin "30") (pinfunction "PD0_30") (pintype "bidirectional"))
    )
    (net (code "28") (name "/SCK") (class "Default")
      (node (ref "J2") (pin "2") (pinfunction "SCK_2") (pintype "passive"))
      (node (ref "J7") (pin "5") (pinfunction "5_5") (pintype "passive"))
      (node (ref "U3") (pin "17") (pinfunction "PB5_17") (pintype "bidirectional"))
    )
    (net (code "29") (name "/SS") (class "Default")
      (node (ref "J7") (pin "8") (pinfunction "8_8") (pintype "passive"))
      (node (ref "U3") (pin "14") (pinfunction "PB2_14") (pintype "bidirectional"))
    )
    (net (code "30") (name "/TX_MCU") (class "Default")
      (node (ref "J4") (pin "2") (pinfunction "2_2") (pintype "passive"))
      (node (ref "R22") (pin "1") (pinfunction "1_1") (pintype "passive"))
      (node (ref "R4") (pin "1") (pinfunction "1_1") (pintype "passive"))
      (node (ref "TP10") (pin "1") (pinfunction "Sgn_1") (pintype "passive"))
      (node (ref "U3") (pin "31") (pinfunction "PD1_31") (pintype "bidirectional"))
    )
    (net (code "31") (name "/V_Current_ADC") (class "Default")
      (node (ref "Q1") (pin "2") (pinfunction "S_2") (pintype "passive"))
      (node (ref "SW7") (pin "2") (pinfunction "2_2") (pintype "passive"))
      (node (ref "U2") (pin "4") (pinfunction "AIN0_4") (pintype "input"))
      (node (ref "U4") (pin "2") (pinfunction "VINA-_2") (pintype "input"))
    )
    (net (code "32") (name "/V_Current_GND") (class "Default")
      (node (ref "R17") (pin "1") (pinfunction "1_1") (pintype "passive"))
      (node (ref "R18") (pin "1") (pinfunction "1_1") (pintype "passive"))
      (node (ref "R20") (pin "2") (pinfunction "2_2") (pintype "passive"))
      (node (ref "U2") (pin "5") (pinfunction "AIN1_5") (pintype "input"))
    )
    (net (code "33") (name "/V_VRM_ADC") (class "Default")
      (node (ref "R14") (pin "1") (pinfunction "1_1") (pintype "passive"))
      (node (ref "R15") (pin "2") (pinfunction "2_2") (pintype "passive"))
      (node (ref "R16") (pin "2") (pinfunction "2_2") (pintype "passive"))
      (node (ref "U2") (pin "6") (pinfunction "AIN2_6") (pintype "input"))
    )
    (net (code "34") (name "/V_VRM_GND") (class "Default")
      (node (ref "R15") (pin "1") (pinfunction "1_1") (pintype "passive"))
      (node (ref "R16") (pin "1") (pinfunction "1_1") (pintype "passive"))
      (node (ref "R19") (pin "2") (pinfunction "2_2") (pintype "passive"))
      (node (ref "U2") (pin "7") (pinfunction "AIN3_7") (pintype "input"))
    )
    (net (code "35") (name "5V") (class "Default")
      (node (ref "C1") (pin "2") (pinfunction "2_2") (pintype "passive"))
      (node (ref "C11") (pin "1") (pinfunction "1_1") (pintype "passive"))
      (node (ref "C2") (pin "2") (pinfunction "2_2") (pintype "passive"))
      (node (ref "C20") (pin "2") (pinfunction "2_2") (pintype "passive"))
      (node (ref "C21") (pin "2") (pinfunction "2_2") (pintype "passive"))
      (node (ref "C23") (pin "2") (pinfunction "2_2") (pintype "passive"))
      (node (ref "C3") (pin "2") (pinfunction "2_2") (pintype "passive"))
      (node (ref "C4") (pin "2") (pinfunction "2_2") (pintype "passive"))
      (node (ref "C8") (pin "2") (pinfunction "2_2") (pintype "passive"))
      (node (ref "D1") (pin "5") (pinfunction "VCC_5") (pintype "passive"))
      (node (ref "D2") (pin "1") (pinfunction "VDD_1") (pintype "input"))
      (node (ref "D3") (pin "1") (pinfunction "VDD_1") (pintype "input"))
      (node (ref "D4") (pin "1") (pinfunction "VDD_1") (pintype "input"))
      (node (ref "D5") (pin "1") (pinfunction "VDD_1") (pintype "input"))
      (node (ref "J2") (pin "4") (pinfunction "VCC_4") (pintype "passive"))
      (node (ref "J6") (pin "1") (pinfunction "1_1") (pintype "passive"))
      (node (ref "J6") (pin "4") (pinfunction "4_4") (pintype "passive"))
      (node (ref "J6") (pin "7") (pinfunction "7_7") (pintype "passive"))
      (node (ref "L1") (pin "1") (pinfunction "1_1") (pintype "passive"))
      (node (ref "LED5") (pin "1") (pinfunction "1_1") (pintype "passive"))
      (node (ref "LED6") (pin "1") (pinfunction "1_1") (pintype "passive"))
      (node (ref "R1") (pin "2") (pinfunction "2_2") (pintype "passive"))
      (node (ref "R8") (pin "2") (pinfunction "2_2") (pintype "passive"))
      (node (ref "TP5") (pin "1") (pinfunction "Sgn_1") (pintype "passive"))
      (node (ref "U1") (pin "16") (pinfunction "VCC_16") (pintype "passive"))
      (node (ref "U2") (pin "8") (pinfunction "VDD_8") (pintype "power_in"))
      (node (ref "U3") (pin "4") (pinfunction "VCC_4") (pintype "power_in"))
      (node (ref "U3") (pin "6") (pinfunction "VCC_6") (pintype "power_in"))
      (node (ref "U4") (pin "8") (pinfunction "VDD_8") (pintype "passive"))
      (node (ref "U5") (pin "3") (pinfunction "VDD_3") (pintype "passive"))
    )
    (net (code "36") (name "5V_Power_Jack") (class "Default")
      (node (ref "C5") (pin "2") (pinfunction "2_2") (pintype "passive"))
      (node (ref "LED1") (pin "1") (pinfunction "1_1") (pintype "passive"))
      (node (ref "P1") (pin "1") (pinfunction "1_1") (pintype "power_in"))
      (node (ref "SW3") (pin "1") (pinfunction "1_1") (pintype "passive"))
      (node (ref "TP1") (pin "1") (pinfunction "Sgn_1") (pintype "passive"))
    )
    (net (code "37") (name "GND") (class "Default")
      (node (ref "BZ1") (pin "1") (pinfunction "BZ1_1") (pintype "passive"))
      (node (ref "C1") (pin "1") (pinfunction "1_1") (pintype "passive"))
      (node (ref "C10") (pin "1") (pinfunction "1_1") (pintype "passive"))
      (node (ref "C11") (pin "2") (pinfunction "2_2") (pintype "passive"))
      (node (ref "C12") (pin "1") (pinfunction "1_1") (pintype "passive"))
      (node (ref "C13") (pin "1") (pinfunction "1_1") (pintype "passive"))
      (node (ref "C16") (pin "1") (pinfunction "1_1") (pintype "passive"))
      (node (ref "C17") (pin "1") (pinfunction "1_1") (pintype "passive"))
      (node (ref "C18") (pin "1") (pinfunction "1_1") (pintype "passive"))
      (node (ref "C19") (pin "1") (pinfunction "1_1") (pintype "passive"))
      (node (ref "C2") (pin "1") (pinfunction "1_1") (pintype "passive"))
      (node (ref "C20") (pin "1") (pinfunction "1_1") (pintype "passive"))
      (node (ref "C21") (pin "1") (pinfunction "1_1") (pintype "passive"))
      (node (ref "C22") (pin "1") (pinfunction "1_1") (pintype "passive"))
      (node (ref "C23") (pin "1") (pinfunction "1_1") (pintype "passive"))
      (node (ref "C3") (pin "1") (pinfunction "1_1") (pintype "passive"))
      (node (ref "C4") (pin "1") (pinfunction "1_1") (pintype "passive"))
      (node (ref "C5") (pin "1") (pinfunction "1_1") (pintype "passive"))
      (node (ref "C7") (pin "1") (pinfunction "1_1") (pintype "passive"))
      (node (ref "C8") (pin "1") (pinfunction "1_1") (pintype "passive"))
      (node (ref "C9") (pin "1") (pinfunction "1_1") (pintype "passive"))
      (node (ref "D1") (pin "2") (pinfunction "GND_2") (pintype "passive"))
      (node (ref "D2") (pin "3") (pinfunction "VSS_3") (pintype "input"))
      (node (ref "D3") (pin "3") (pinfunction "VSS_3") (pintype "input"))
      (node (ref "D4") (pin "3") (pinfunction "VSS_3") (pintype "input"))
      (node (ref "D5") (pin "3") (pinfunction "VSS_3") (pintype "input"))
      (node (ref "J1") (pin "5") (pinfunction "GND_5") (pintype "passive"))
      (node (ref "J1") (pin "6") (pinfunction "SHIELD_6") (pintype "passive"))
      (node (ref "J1") (pin "7") (pinfunction "SHIELD_7") (pintype "passive"))
      (node (ref "J1") (pin "8") (pinfunction "SHIELD_8") (pintype "passive"))
      (node (ref "J1") (pin "9") (pinfunction "SHIELD_9") (pintype "passive"))
      (node (ref "J2") (pin "6") (pinfunction "GND_6") (pintype "passive"))
      (node (ref "J3") (pin "5") (pinfunction "GND_5") (pintype "passive"))
      (node (ref "J3") (pin "6") (pinfunction "SHIELD_6") (pintype "passive"))
      (node (ref "J3") (pin "7") (pinfunction "SHIELD_7") (pintype "passive"))
      (node (ref "J3") (pin "8") (pinfunction "SHIELD_8") (pintype "passive"))
      (node (ref "J3") (pin "9") (pinfunction "SHIELD_9") (pintype "passive"))
      (node (ref "J6") (pin "2") (pinfunction "2_2") (pintype "passive"))
      (node (ref "J6") (pin "3") (pinfunction "3_3") (pintype "passive"))
      (node (ref "J7") (pin "4") (pinfunction "4_4") (pintype "passive"))
      (node (ref "P1") (pin "2") (pinfunction "2_2") (pintype "power_in"))
      (node (ref "P1") (pin "3") (pinfunction "3_3") (pintype "power_in"))
      (node (ref "P2") (pin "2") (pinfunction "GND_2") (pintype "passive"))
      (node (ref "P3") (pin "2") (pinfunction "2_2") (pintype "power_in"))
      (node (ref "P3") (pin "3") (pinfunction "3_3") (pintype "power_in"))
      (node (ref "R12") (pin "1") (pinfunction "1_1") (pintype "passive"))
      (node (ref "R13") (pin "1") (pinfunction "1_1") (pintype "passive"))
      (node (ref "R19") (pin "1") (pinfunction "1_1") (pintype "passive"))
      (node (ref "R20") (pin "1") (pinfunction "1_1") (pintype "passive"))
      (node (ref "R23") (pin "1") (pinfunction "1_1") (pintype "passive"))
      (node (ref "R24") (pin "1") (pinfunction "1_1") (pintype "passive"))
      (node (ref "R5") (pin "1") (pinfunction "1_1") (pintype "passive"))
      (node (ref "R6") (pin "2") (pinfunction "2_2") (pintype "passive"))
      (node (ref "R9") (pin "1") (pinfunction "1_1") (pintype "passive"))
      (node (ref "SW1") (pin "3") (pinfunction "3_3") (pintype "passive"))
      (node (ref "SW1") (pin "4") (pinfunction "4_4") (pintype "passive"))
      (node (ref "TP1") (pin "2") (pinfunction "Gnd_2") (pintype "passive"))
      (node (ref "TP10") (pin "2") (pinfunction "Gnd_2") (pintype "passive"))
      (node (ref "TP2") (pin "2") (pinfunction "Gnd_2") (pintype "passive"))
      (node (ref "TP3") (pin "2") (pinfunction "Gnd_2") (pintype "passive"))
      (node (ref "TP5") (pin "2") (pinfunction "Gnd_2") (pintype "passive"))
      (node (ref "TP6") (pin "2") (pinfunction "Gnd_2") (pintype "passive"))
      (node (ref "TP7") (pin "2") (pinfunction "Gnd_2") (pintype "passive"))
      (node (ref "TP8") (pin "2") (pinfunction "Gnd_2") (pintype "passive"))
      (node (ref "TP9") (pin "2") (pinfunction "Gnd_2") (pintype "passive"))
      (node (ref "U1") (pin "1") (pinfunction "GND_1") (pintype "passive"))
      (node (ref "U2") (pin "3") (pinfunction "GND_3") (pintype "power_in"))
      (node (ref "U3") (pin "21") (pinfunction "GND_21") (pintype "power_in"))
      (node (ref "U3") (pin "3") (pinfunction "GND_3") (pintype "power_in"))
      (node (ref "U3") (pin "5") (pinfunction "GND_5") (pintype "power_in"))
      (node (ref "U4") (pin "4") (pinfunction "VSS_4") (pintype "passive"))
      (node (ref "U4") (pin "5") (pinfunction "VINB+_5") (pintype "input"))
      (node (ref "U4") (pin "6") (pinfunction "VINB-_6") (pintype "input"))
      (node (ref "U5") (pin "2") (pinfunction "VSS_2") (pintype "passive"))
      (node (ref "Y1") (pin "2") (pinfunction "GND_2") (pintype "passive"))
      (node (ref "Y1") (pin "4") (pinfunction "GND_4") (pintype "passive"))
      (node (ref "Y2") (pin "2") (pinfunction "GND_2") (pintype "passive"))
      (node (ref "Y2") (pin "4") (pinfunction "GND_4") (pintype "passive"))
    )
    (net (code "38") (name "Net-(D2-DIN)") (class "Default")
      (node (ref "D2") (pin "4") (pinfunction "DIN_4") (pintype "input"))
      (node (ref "D3") (pin "2") (pinfunction "DOUT_2") (pintype "output"))
    )
    (net (code "39") (name "Net-(D3-DIN)") (class "Default")
      (node (ref "D3") (pin "4") (pinfunction "DIN_4") (pintype "input"))
      (node (ref "D4") (pin "2") (pinfunction "DOUT_2") (pintype "output"))
    )
    (net (code "40") (name "Net-(D4-DIN)") (class "Default")
      (node (ref "D4") (pin "4") (pinfunction "DIN_4") (pintype "input"))
      (node (ref "D5") (pin "2") (pinfunction "DOUT_2") (pintype "output"))
    )
    (net (code "41") (name "Net-(D5-DIN)") (class "Default")
      (node (ref "D5") (pin "4") (pinfunction "DIN_4") (pintype "input"))
      (node (ref "R2") (pin "1") (pinfunction "1_1") (pintype "passive"))
    )
    (net (code "42") (name "Net-(J3-VBUS)") (class "Default")
      (node (ref "J3") (pin "1") (pinfunction "VBUS_1") (pintype "passive"))
      (node (ref "SW4") (pin "1") (pinfunction "1_1") (pintype "passive"))
    )
    (net (code "43") (name "Net-(LED1-Pad2)") (class "Default")
      (node (ref "LED1") (pin "2") (pinfunction "2_2") (pintype "passive"))
      (node (ref "R5") (pin "2") (pinfunction "2_2") (pintype "passive"))
    )
    (net (code "44") (name "Net-(LED2-Pad2)") (class "Default")
      (node (ref "LED2") (pin "2") (pinfunction "2_2") (pintype "passive"))
      (node (ref "R6") (pin "1") (pinfunction "1_1") (pintype "passive"))
    )
    (net (code "45") (name "Net-(LED4-Pad2)") (class "Default")
      (node (ref "LED4") (pin "2") (pinfunction "2_2") (pintype "passive"))
      (node (ref "R13") (pin "2") (pinfunction "2_2") (pintype "passive"))
    )
    (net (code "46") (name "Net-(LED5-Pad2)") (class "Default")
      (node (ref "LED5") (pin "2") (pinfunction "2_2") (pintype "passive"))
      (node (ref "R21") (pin "2") (pinfunction "2_2") (pintype "passive"))
    )
    (net (code "47") (name "Net-(LED6-Pad2)") (class "Default")
      (node (ref "LED6") (pin "2") (pinfunction "2_2") (pintype "passive"))
      (node (ref "R22") (pin "2") (pinfunction "2_2") (pintype "passive"))
    )
    (net (code "48") (name "Net-(LED7-Pad2)") (class "Default")
      (node (ref "LED7") (pin "2") (pinfunction "2_2") (pintype "passive"))
      (node (ref "R23") (pin "2") (pinfunction "2_2") (pintype "passive"))
    )
    (net (code "49") (name "Net-(LED8-Pad2)") (class "Default")
      (node (ref "LED8") (pin "2") (pinfunction "2_2") (pintype "passive"))
      (node (ref "R24") (pin "2") (pinfunction "2_2") (pintype "passive"))
    )
    (net (code "50") (name "Net-(P2-POWER)") (class "Default")
      (node (ref "P2") (pin "1") (pinfunction "POWER_1") (pintype "passive"))
      (node (ref "SW5") (pin "1") (pinfunction "1_1") (pintype "passive"))
    )
    (net (code "51") (name "Net-(P3-Pad1)") (class "Default")
      (node (ref "P3") (pin "1") (pinfunction "1_1") (pintype "power_in"))
      (node (ref "SW6") (pin "1") (pinfunction "1_1") (pintype "passive"))
    )
    (net (code "52") (name "Net-(Q1-G)") (class "Default")
      (node (ref "Q1") (pin "1") (pinfunction "G_1") (pintype "passive"))
      (node (ref "U4") (pin "1") (pinfunction "VOUTA_1") (pintype "output"))
    )
    (net (code "53") (name "Net-(R17-Pad2)") (class "Default")
      (node (ref "R17") (pin "2") (pinfunction "2_2") (pintype "passive"))
      (node (ref "SW7") (pin "1") (pinfunction "1_1") (pintype "passive"))
    )
    (net (code "54") (name "Net-(R18-Pad2)") (class "Default")
      (node (ref "R18") (pin "2") (pinfunction "2_2") (pintype "passive"))
      (node (ref "SW7") (pin "3") (pinfunction "3_3") (pintype "passive"))
    )
    (net (code "55") (name "Net-(TP3-Sgn)") (class "Default")
      (node (ref "R8") (pin "1") (pinfunction "1_1") (pintype "passive"))
      (node (ref "SW3") (pin "2") (pinfunction "2_2") (pintype "passive"))
      (node (ref "TP3") (pin "1") (pinfunction "Sgn_1") (pintype "passive"))
    )
    (net (code "56") (name "Net-(U1-RXD)") (class "Default")
      (node (ref "R4") (pin "2") (pinfunction "2_2") (pintype "passive"))
      (node (ref "U1") (pin "3") (pinfunction "RXD_3") (pintype "passive"))
    )
    (net (code "57") (name "Net-(U1-TXD)") (class "Default")
      (node (ref "R3") (pin "2") (pinfunction "2_2") (pintype "passive"))
      (node (ref "U1") (pin "2") (pinfunction "TXD_2") (pintype "passive"))
    )
    (net (code "58") (name "Net-(U1-V3)") (class "Default")
      (node (ref "C10") (pin "2") (pinfunction "2_2") (pintype "passive"))
      (node (ref "U1") (pin "4") (pinfunction "V3_4") (pintype "passive"))
    )
    (net (code "59") (name "Net-(U2-ADDR)") (class "Default")
      (node (ref "R9") (pin "2") (pinfunction "2_2") (pintype "passive"))
      (node (ref "U2") (pin "1") (pinfunction "ADDR_1") (pintype "passive"))
    )
    (net (code "60") (name "Net-(U4-VINA+)") (class "Default")
      (node (ref "U4") (pin "3") (pinfunction "VINA+_3") (pintype "input"))
      (node (ref "U5") (pin "1") (pinfunction "VOUT_1") (pintype "passive"))
    )
    (net (code "61") (name "Net-(U5-A0)") (class "Default")
      (node (ref "R12") (pin "2") (pinfunction "2_2") (pintype "passive"))
      (node (ref "U5") (pin "6") (pinfunction "A0_6") (pintype "passive"))
    )
    (net (code "62") (name "VRM_IN") (class "Default")
      (node (ref "C19") (pin "2") (pinfunction "2_2") (pintype "passive"))
      (node (ref "C22") (pin "2") (pinfunction "2_2") (pintype "passive"))
      (node (ref "LED4") (pin "1") (pinfunction "1_1") (pintype "passive"))
      (node (ref "Q1") (pin "3") (pinfunction "D_3") (pintype "passive"))
      (node (ref "R14") (pin "2") (pinfunction "2_2") (pintype "passive"))
      (node (ref "SW4") (pin "2") (pinfunction "2_2") (pintype "passive"))
      (node (ref "SW5") (pin "2") (pinfunction "2_2") (pintype "passive"))
      (node (ref "SW6") (pin "2") (pinfunction "2_2") (pintype "passive"))
      (node (ref "TP6") (pin "1") (pinfunction "Sgn_1") (pintype "passive"))
    )
    (net (code "63") (name "VUSB_5V") (class "Default")
      (node (ref "C7") (pin "2") (pinfunction "2_2") (pintype "passive"))
      (node (ref "J1") (pin "1") (pinfunction "VBUS_1") (pintype "passive"))
      (node (ref "LED2") (pin "1") (pinfunction "1_1") (pintype "passive"))
      (node (ref "SW3") (pin "3") (pinfunction "3_3") (pintype "passive"))
    )
    (net (code "64") (name "unconnected-(D1-IO-3-Pad4)") (class "Default")
      (node (ref "D1") (pin "4") (pinfunction "IO-3_4") (pintype "passive"))
    )
    (net (code "65") (name "unconnected-(D1-IO-4-Pad6)") (class "Default")
      (node (ref "D1") (pin "6") (pinfunction "IO-4_6") (pintype "passive"))
    )
    (net (code "66") (name "unconnected-(D2-DOUT-Pad2)") (class "Default")
      (node (ref "D2") (pin "2") (pinfunction "DOUT_2") (pintype "output"))
    )
    (net (code "67") (name "unconnected-(J1-ID-Pad4)") (class "Default")
      (node (ref "J1") (pin "4") (pinfunction "ID_4") (pintype "passive"))
    )
    (net (code "68") (name "unconnected-(J3-D+-Pad3)") (class "Default")
      (node (ref "J3") (pin "3") (pinfunction "D+_3") (pintype "passive"))
    )
    (net (code "69") (name "unconnected-(J3-D--Pad2)") (class "Default")
      (node (ref "J3") (pin "2") (pinfunction "D-_2") (pintype "passive"))
    )
    (net (code "70") (name "unconnected-(J3-ID-Pad4)") (class "Default")
      (node (ref "J3") (pin "4") (pinfunction "ID_4") (pintype "passive"))
    )
    (net (code "71") (name "unconnected-(J6-Pad5)") (class "Default")
      (node (ref "J6") (pin "5") (pinfunction "5_5") (pintype "passive"))
    )
    (net (code "72") (name "unconnected-(J6-Pad8)") (class "Default")
      (node (ref "J6") (pin "8") (pinfunction "8_8") (pintype "passive"))
    )
    (net (code "73") (name "unconnected-(U1-CTS#-Pad9)") (class "Default")
      (node (ref "U1") (pin "9") (pinfunction "CTS#_9") (pintype "passive"))
    )
    (net (code "74") (name "unconnected-(U1-DCD#-Pad12)") (class "Default")
      (node (ref "U1") (pin "12") (pinfunction "DCD#_12") (pintype "passive"))
    )
    (net (code "75") (name "unconnected-(U1-DSR#-Pad10)") (class "Default")
      (node (ref "U1") (pin "10") (pinfunction "DSR#_10") (pintype "passive"))
    )
    (net (code "76") (name "unconnected-(U1-RI#-Pad11)") (class "Default")
      (node (ref "U1") (pin "11") (pinfunction "RI#_11") (pintype "passive"))
    )
    (net (code "77") (name "unconnected-(U1-RS232-Pad15)") (class "Default")
      (node (ref "U1") (pin "15") (pinfunction "RS232_15") (pintype "passive"))
    )
    (net (code "78") (name "unconnected-(U1-RTS#-Pad14)") (class "Default")
      (node (ref "U1") (pin "14") (pinfunction "RTS#_14") (pintype "passive"))
    )
    (net (code "79") (name "unconnected-(U2-ALERT{slash}RDY-Pad2)") (class "Default")
      (node (ref "U2") (pin "2") (pinfunction "ALERT/RDY_2") (pintype "output"))
    )
    (net (code "80") (name "unconnected-(U3-ADC6-Pad19)") (class "Default")
      (node (ref "U3") (pin "19") (pinfunction "ADC6_19") (pintype "bidirectional"))
    )
    (net (code "81") (name "unconnected-(U3-ADC7-Pad22)") (class "Default")
      (node (ref "U3") (pin "22") (pinfunction "ADC7_22") (pintype "bidirectional"))
    )
    (net (code "82") (name "unconnected-(U4-VOUTB-Pad7)") (class "Default")
      (node (ref "U4") (pin "7") (pinfunction "VOUTB_7") (pintype "output"))
    )
  )
)
